# RS232.net
KiCad netlist of a schematic drawn in Altium Designer
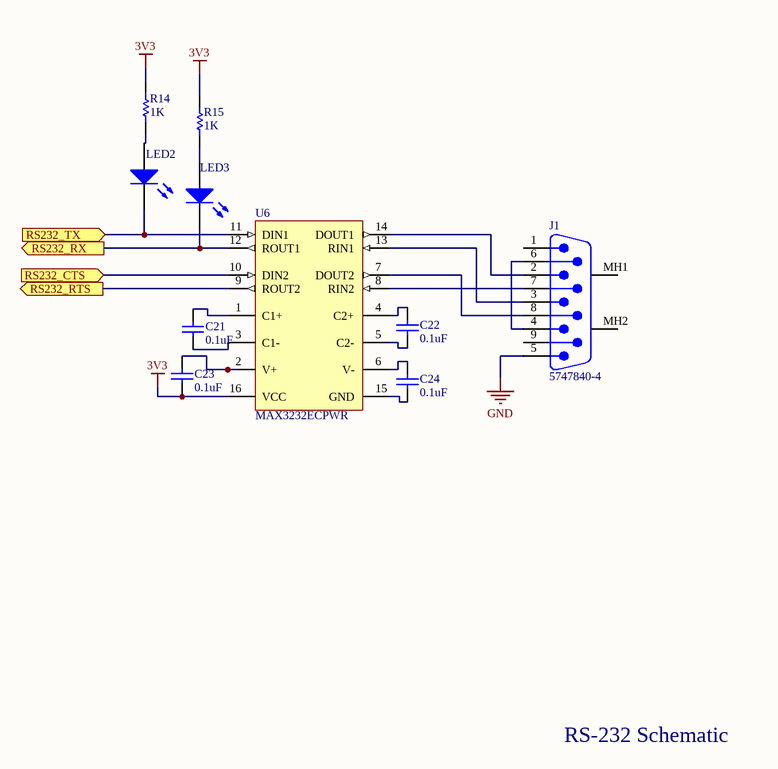
[diagram p0: RS232.SchDoc]

(export (version "E")
  (design (tool "Eeschema 10.0.6"))
  (components
    (comp (ref "C21")
      (value "0.1uF")
      (footprint "CAPC1608X90X35LL15T15")
      (description "Chip Capacitor, 100 nF, +/- 10%, 50 V, -55 to 125 degC, 0603 (1608 Metric), RoHS, Tape and Reel")
      (fields (field (name "TOLERANCE") "10%"))
      (libsource (lib "Altium Content Vault") (part "CAP-NP-2"))
    )
    (comp (ref "C22")
      (value "0.1uF")
      (footprint "CAPC1608X90X35LL15T15")
      (description "Chip Capacitor, 100 nF, +/- 10%, 50 V, -55 to 125 degC, 0603 (1608 Metric), RoHS, Tape and Reel")
      (fields (field (name "TOLERANCE") "10%"))
      (libsource (lib "Altium Content Vault") (part "CAP-NP-2"))
    )
    (comp (ref "C23")
      (value "0.1uF")
      (footprint "CAPC1608X90X35ML15T15")
      (description "Chip Capacitor, 100 nF, +/- 10%, 50 V, -55 to 125 degC, 0603 (1608 Metric), RoHS, Tape and Reel")
      (fields (field (name "TOLERANCE") "10%"))
      (libsource (lib "Altium Content Vault") (part "CAP-NP-2"))
    )
    (comp (ref "C24")
      (value "0.1uF")
      (footprint "CAPC1608X90X35LL15T15")
      (description "Chip Capacitor, 100 nF, +/- 10%, 50 V, -55 to 125 degC, 0603 (1608 Metric), RoHS, Tape and Reel")
      (fields (field (name "TOLERANCE") "10%"))
      (libsource (lib "Altium Content Vault") (part "CAP-NP-2"))
    )
    (comp (ref "J1")
      (value "5747840-4")
      (footprint "TECO-5747840-4_V")
      (fields (field (name "MANUFACTURER") "TE Connectivity"))
      (libsource (lib "Altium Content Vault") (part "CN-2S-2M-D9"))
    )
    (comp (ref "LED2")
      (value "~")
      (footprint "1204")
      (description "SMD Side view mono-color Chip LED-Round , WL-SMSW, Green")
      (fields (field (name "PARTNUMBER") "155124GS73200") (field (name "MANUFACTURER") "Wuerth Elektronik"))
      (libsource (lib "Altium Content Vault") (part "WE-LED_K1A2-2"))
    )
    (comp (ref "LED3")
      (value "~")
      (footprint "1204")
      (description "SMD Side view mono-color Chip LED-Round , WL-SMSW, Green")
      (fields (field (name "PARTNUMBER") "155124GS73200") (field (name "MANUFACTURER") "Wuerth Elektronik"))
      (libsource (lib "Altium Content Vault") (part "WE-LED_K1A2-2"))
    )
    (comp (ref "R14")
      (value "1K")
      (footprint "RESC2013X60X30ML20T20")
      (fields (field (name "PART NUMBER") "RK73B2ATTD102J") (field (name "MANUFACTURER") "KOA Speer"))
      (libsource (lib "Altium Content Vault") (part "RES"))
    )
    (comp (ref "R15")
      (value "1K")
      (footprint "RESC2013X60X30ML20T20")
      (fields (field (name "PART NUMBER") "RK73B2ATTD102J") (field (name "MANUFACTURER") "KOA Speer"))
      (libsource (lib "Altium Content Vault") (part "RES"))
    )
    (comp (ref "U6")
      (value "MAX3232ECPWR")
      (footprint "PW0016A_M")
      (libsource (lib "Altium Content Vault") (part "TI-MAX3232E-TSSOP_PW-16"))
    )
  )
  (nets
    (net (code "1") (name "/RS232_CTS") (class "Default")
      (node (ref "U6") (pin "10") (pinfunction "DIN2_10") (pintype "input"))
    )
    (net (code "2") (name "/RS232_RTS") (class "Default")
      (node (ref "U6") (pin "9") (pinfunction "ROUT2_9") (pintype "output"))
    )
    (net (code "3") (name "/RS232_RX") (class "Default")
      (node (ref "LED3") (pin "1") (pinfunction "K_1") (pintype "passive"))
      (node (ref "U6") (pin "12") (pinfunction "ROUT1_12") (pintype "output"))
    )
    (net (code "4") (name "/RS232_TX") (class "Default")
      (node (ref "LED2") (pin "1") (pinfunction "K_1") (pintype "passive"))
      (node (ref "U6") (pin "11") (pinfunction "DIN1_11") (pintype "input"))
    )
    (net (code "5") (name "3V3") (class "Default")
      (node (ref "C23") (pin "1") (pinfunction "1_1") (pintype "passive"))
      (node (ref "R14") (pin "1") (pinfunction "1_1") (pintype "passive"))
      (node (ref "R15") (pin "1") (pinfunction "1_1") (pintype "passive"))
      (node (ref "U6") (pin "16") (pinfunction "VCC_16") (pintype "power_in"))
    )
    (net (code "6") (name "GND") (class "Default")
      (node (ref "J1") (pin "5") (pinfunction "5_5") (pintype "passive"))
    )
    (net (code "7") (name "Net-(J1-Pad4)") (class "Default")
      (node (ref "J1") (pin "4") (pinfunction "4_4") (pintype "passive"))
      (node (ref "J1") (pin "6") (pinfunction "6_6") (pintype "passive"))
    )
    (net (code "8") (name "Net-(LED2-A)") (class "Default")
      (node (ref "LED2") (pin "2") (pinfunction "A_2") (pintype "passive"))
      (node (ref "R14") (pin "2") (pinfunction "2_2") (pintype "passive"))
    )
    (net (code "9") (name "Net-(LED3-A)") (class "Default")
      (node (ref "LED3") (pin "2") (pinfunction "A_2") (pintype "passive"))
      (node (ref "R15") (pin "2") (pinfunction "2_2") (pintype "passive"))
    )
    (net (code "10") (name "Net-(U6-C1+)") (class "Default")
      (node (ref "C21") (pin "2") (pinfunction "2_2") (pintype "passive"))
      (node (ref "U6") (pin "1") (pinfunction "C1+_1") (pintype "passive"))
    )
    (net (code "11") (name "Net-(U6-C1-)") (class "Default")
      (node (ref "C21") (pin "1") (pinfunction "1_1") (pintype "passive"))
      (node (ref "U6") (pin "3") (pinfunction "C1-_3") (pintype "passive"))
    )
    (net (code "12") (name "Net-(U6-C2+)") (class "Default")
      (node (ref "C22") (pin "2") (pinfunction "2_2") (pintype "passive"))
      (node (ref "U6") (pin "4") (pinfunction "C2+_4") (pintype "passive"))
    )
    (net (code "13") (name "Net-(U6-C2-)") (class "Default")
      (node (ref "C22") (pin "1") (pinfunction "1_1") (pintype "passive"))
      (node (ref "U6") (pin "5") (pinfunction "C2-_5") (pintype "passive"))
    )
    (net (code "14") (name "Net-(U6-DOUT1)") (class "Default")
      (node (ref "J1") (pin "2") (pinfunction "2_2") (pintype "passive"))
      (node (ref "U6") (pin "14") (pinfunction "DOUT1_14") (pintype "output"))
    )
    (net (code "15") (name "Net-(U6-DOUT2)") (class "Default")
      (node (ref "J1") (pin "8") (pinfunction "8_8") (pintype "passive"))
      (node (ref "U6") (pin "7") (pinfunction "DOUT2_7") (pintype "output"))
    )
    (net (code "16") (name "Net-(U6-GND)") (class "Default")
      (node (ref "C24") (pin "1") (pinfunction "1_1") (pintype "passive"))
      (node (ref "U6") (pin "15") (pinfunction "GND_15") (pintype "power_in"))
    )
    (net (code "17") (name "Net-(U6-RIN1)") (class "Default")
      (node (ref "J1") (pin "3") (pinfunction "3_3") (pintype "passive"))
      (node (ref "U6") (pin "13") (pinfunction "RIN1_13") (pintype "input"))
    )
    (net (code "18") (name "Net-(U6-RIN2)") (class "Default")
      (node (ref "J1") (pin "7") (pinfunction "7_7") (pintype "passive"))
      (node (ref "U6") (pin "8") (pinfunction "RIN2_8") (pintype "input"))
    )
    (net (code "19") (name "Net-(U6-V+)") (class "Default")
      (node (ref "C23") (pin "2") (pinfunction "2_2") (pintype "passive"))
      (node (ref "U6") (pin "2") (pinfunction "V+_2") (pintype "power_in"))
    )
    (net (code "20") (name "Net-(U6-V-)") (class "Default")
      (node (ref "C24") (pin "2") (pinfunction "2_2") (pintype "passive"))
      (node (ref "U6") (pin "6") (pinfunction "V-_6") (pintype "power_in"))
    )
    (net (code "21") (name "unconnected-(J1-Pad1)") (class "Default")
      (node (ref "J1") (pin "1") (pinfunction "1_1") (pintype "passive"))
    )
    (net (code "22") (name "unconnected-(J1-Pad9)") (class "Default")
      (node (ref "J1") (pin "9") (pinfunction "9_9") (pintype "passive"))
    )
    (net (code "23") (name "unconnected-(J1-PadMH1)") (class "Default")
      (node (ref "J1") (pin "MH1") (pinfunction "MH1_MH1") (pintype "passive"))
    )
    (net (code "24") (name "unconnected-(J1-PadMH2)") (class "Default")
      (node (ref "J1") (pin "MH2") (pinfunction "MH2_MH2") (pintype "passive"))
    )
  )
)
